# 3V3_REG.net
KiCad netlist of a schematic drawn in Altium Designer
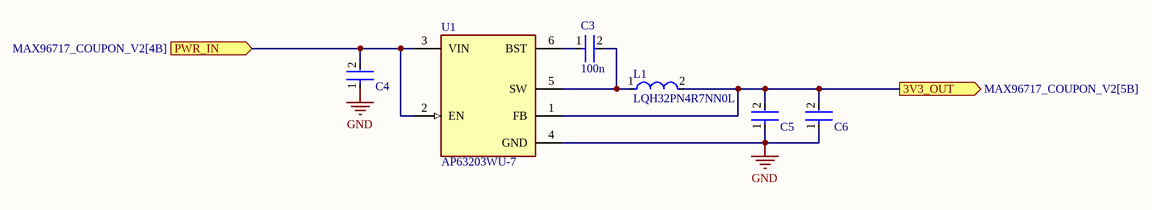
[diagram p0: 3V3_REG.SchDoc]

(export (version "E")
  (design (tool "Eeschema 10.0.6"))
  (components
    (comp (ref "C3")
      (value "100n")
      (footprint "FP-0402-L_1_0_0_05-W_0_5-IPC_A")
      (description "LARGE PADS, 0402 CAP, CHANGE COMMENT TO MATCH REAL P/N")
      (libsource (lib "Space Concordia") (part "b4654b650e69147ec39a6b967a45e02"))
    )
    (comp (ref "C4")
      (value "GRM21BR61E226ME44L")
      (footprint "FP-GRM21B-0_2-e0_2_0_7-IPC_B")
      (description "Chip Multilayer Ceramic Capacitors for General Purpose, 0805, 22uF, X5R, 15%, 20%, 25V")
      (fields (field (name "TOLERANCE") "20%") (field (name "VOLTAGE") "25V"))
      (libsource (lib "Altium Content Vault") (part "b4654b650e69147ec39a6b967a45e02"))
    )
    (comp (ref "C5")
      (value "GRM21BR61E226ME44L")
      (footprint "FP-GRM21B-0_2-e0_2_0_7-IPC_B")
      (description "Chip Multilayer Ceramic Capacitors for General Purpose, 0805, 22uF, X5R, 15%, 20%, 25V")
      (fields (field (name "TOLERANCE") "20%") (field (name "VOLTAGE") "25V"))
      (libsource (lib "Altium Content Vault") (part "b4654b650e69147ec39a6b967a45e02"))
    )
    (comp (ref "C6")
      (value "GRM21BR61E226ME44L")
      (footprint "FP-GRM21B-0_2-e0_2_0_7-IPC_B")
      (description "Chip Multilayer Ceramic Capacitors for General Purpose, 0805, 22uF, X5R, 15%, 20%, 25V")
      (fields (field (name "TOLERANCE") "20%") (field (name "VOLTAGE") "25V"))
      (libsource (lib "Altium Content Vault") (part "b4654b650e69147ec39a6b967a45e02"))
    )
    (comp (ref "L1")
      (value "LQH32PN4R7NN0L")
      (footprint "FP-LQH32PB_N0-MFG")
      (description "Wire Wound Ferrite Inductor for Power Lines 4.7μH ±30% 0.216Ω 1000mA 1210")
      (fields (field (name "TOLERANCE") "30%"))
      (libsource (lib "Altium Content Vault") (part "725321dda6339637d4d059423bc1c3c"))
    )
    (comp (ref "U1")
      (value "AP63203WU-7")
      (footprint "FP-TSOT26-MFG")
      (description "IC REG BUCK 3.3V 2A TSOT26")
      (fields
        (field (name "MANUFACTURER") "Diodes Inc.")
        (field (name "OCTOPART") "https://octopart.com/ap63203wu-7-diodes+inc.-98099550")
      )
      (libsource (lib "Altium Content Vault") (part "0e61c2974d7114b43f01ef96ae2e524"))
    )
  )
  (nets
    (net (code "1") (name "/3V3_OUT") (class "Default")
      (node (ref "C5") (pin "2") (pinfunction "2_2") (pintype "passive"))
      (node (ref "C6") (pin "2") (pinfunction "2_2") (pintype "passive"))
      (node (ref "L1") (pin "2") (pinfunction "2_2") (pintype "passive"))
      (node (ref "U1") (pin "1") (pinfunction "FB_1") (pintype "passive"))
    )
    (net (code "2") (name "/PWR_IN") (class "Default")
      (node (ref "C4") (pin "2") (pinfunction "2_2") (pintype "passive"))
      (node (ref "U1") (pin "2") (pinfunction "EN_2") (pintype "input"))
      (node (ref "U1") (pin "3") (pinfunction "VIN_3") (pintype "power_in"))
    )
    (net (code "3") (name "GND") (class "Default")
      (node (ref "C4") (pin "1") (pinfunction "1_1") (pintype "passive"))
      (node (ref "C5") (pin "1") (pinfunction "1_1") (pintype "passive"))
      (node (ref "C6") (pin "1") (pinfunction "1_1") (pintype "passive"))
      (node (ref "U1") (pin "4") (pinfunction "GND_4") (pintype "power_in"))
    )
    (net (code "4") (name "Net-(U1-BST)") (class "Default")
      (node (ref "C3") (pin "1") (pinfunction "1_1") (pintype "passive"))
      (node (ref "U1") (pin "6") (pinfunction "BST_6") (pintype "passive"))
    )
    (net (code "5") (name "Net-(U1-SW)") (class "Default")
      (node (ref "C3") (pin "2") (pinfunction "2_2") (pintype "passive"))
      (node (ref "L1") (pin "1") (pinfunction "1_1") (pintype "passive"))
      (node (ref "U1") (pin "5") (pinfunction "SW_5") (pintype "passive"))
    )
  )
)
